# BottomButtonBoard.net
KiCad netlist of a schematic drawn in EAGLE
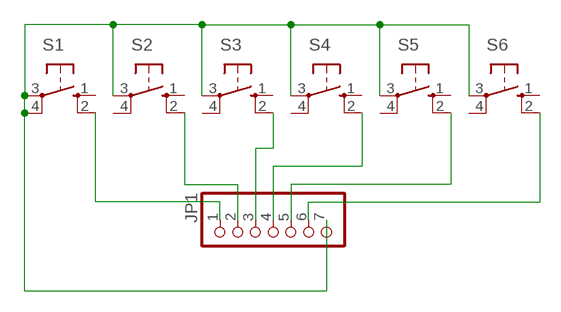
[diagram p0: schematic, sheet 1]

(export (version "E")
  (design (tool "Eeschema 10.0.6"))
  (components
    (comp (ref "JP1")
      (value "PINHD-1X7")
      (footprint "eagle-import:1X07")
      (libsource (lib "eagle-import") (part "PINHD-1X7"))
    )
    (comp (ref "S1")
      (value "10-XX")
      (footprint "eagle-import:B3F-10XX")
      (fields (field (name "MPN") "B3F-1000"))
      (libsource (lib "eagle-import") (part "10-XX"))
    )
    (comp (ref "S2")
      (value "10-XX")
      (footprint "eagle-import:B3F-10XX")
      (fields (field (name "MPN") "B3F-1000"))
      (libsource (lib "eagle-import") (part "10-XX"))
    )
    (comp (ref "S3")
      (value "10-XX")
      (footprint "eagle-import:B3F-10XX")
      (fields (field (name "MPN") "B3F-1000"))
      (libsource (lib "eagle-import") (part "10-XX"))
    )
    (comp (ref "S4")
      (value "10-XX")
      (footprint "eagle-import:B3F-10XX")
      (fields (field (name "MPN") "B3F-1000"))
      (libsource (lib "eagle-import") (part "10-XX"))
    )
    (comp (ref "S5")
      (value "10-XX")
      (footprint "eagle-import:B3F-10XX")
      (fields (field (name "MPN") "B3F-1000"))
      (libsource (lib "eagle-import") (part "10-XX"))
    )
    (comp (ref "S6")
      (value "10-XX")
      (footprint "eagle-import:B3F-10XX")
      (fields (field (name "MPN") "B3F-1000"))
      (libsource (lib "eagle-import") (part "10-XX"))
    )
  )
  (nets
    (net (code "1") (name "Net-(S1-P)") (class "Default")
      (node (ref "JP1") (pin "7") (pinfunction "7_7") (pintype "passive"))
      (node (ref "S1") (pin "3") (pinfunction "P_3") (pintype "passive"))
      (node (ref "S1") (pin "4") (pinfunction "P1_4") (pintype "passive"))
      (node (ref "S2") (pin "3") (pinfunction "P_3") (pintype "passive"))
      (node (ref "S3") (pin "3") (pinfunction "P_3") (pintype "passive"))
      (node (ref "S4") (pin "3") (pinfunction "P_3") (pintype "passive"))
      (node (ref "S5") (pin "3") (pinfunction "P_3") (pintype "passive"))
      (node (ref "S6") (pin "3") (pinfunction "P_3") (pintype "passive"))
    )
    (net (code "2") (name "Net-(S1-S1)") (class "Default")
      (node (ref "JP1") (pin "1") (pinfunction "1_1") (pintype "passive"))
      (node (ref "S1") (pin "2") (pinfunction "S1_2") (pintype "passive"))
    )
    (net (code "3") (name "Net-(S2-S1)") (class "Default")
      (node (ref "JP1") (pin "2") (pinfunction "2_2") (pintype "passive"))
      (node (ref "S2") (pin "2") (pinfunction "S1_2") (pintype "passive"))
    )
    (net (code "4") (name "Net-(S3-S1)") (class "Default")
      (node (ref "JP1") (pin "3") (pinfunction "3_3") (pintype "passive"))
      (node (ref "S3") (pin "2") (pinfunction "S1_2") (pintype "passive"))
    )
    (net (code "5") (name "Net-(S4-S1)") (class "Default")
      (node (ref "JP1") (pin "4") (pinfunction "4_4") (pintype "passive"))
      (node (ref "S4") (pin "2") (pinfunction "S1_2") (pintype "passive"))
    )
    (net (code "6") (name "Net-(S5-S1)") (class "Default")
      (node (ref "JP1") (pin "5") (pinfunction "5_5") (pintype "passive"))
      (node (ref "S5") (pin "2") (pinfunction "S1_2") (pintype "passive"))
    )
    (net (code "7") (name "Net-(S6-S1)") (class "Default")
      (node (ref "JP1") (pin "6") (pinfunction "6_6") (pintype "passive"))
      (node (ref "S6") (pin "2") (pinfunction "S1_2") (pintype "passive"))
    )
    (net (code "8") (name "unconnected-(S1-S-Pad1)") (class "Default")
      (node (ref "S1") (pin "1") (pinfunction "S_1") (pintype "passive"))
    )
    (net (code "9") (name "unconnected-(S2-P1-Pad4)") (class "Default")
      (node (ref "S2") (pin "4") (pinfunction "P1_4") (pintype "passive"))
    )
    (net (code "10") (name "unconnected-(S2-S-Pad1)") (class "Default")
      (node (ref "S2") (pin "1") (pinfunction "S_1") (pintype "passive"))
    )
    (net (code "11") (name "unconnected-(S3-P1-Pad4)") (class "Default")
      (node (ref "S3") (pin "4") (pinfunction "P1_4") (pintype "passive"))
    )
    (net (code "12") (name "unconnected-(S3-S-Pad1)") (class "Default")
      (node (ref "S3") (pin "1") (pinfunction "S_1") (pintype "passive"))
    )
    (net (code "13") (name "unconnected-(S4-P1-Pad4)") (class "Default")
      (node (ref "S4") (pin "4") (pinfunction "P1_4") (pintype "passive"))
    )
    (net (code "14") (name "unconnected-(S4-S-Pad1)") (class "Default")
      (node (ref "S4") (pin "1") (pinfunction "S_1") (pintype "passive"))
    )
    (net (code "15") (name "unconnected-(S5-P1-Pad4)") (class "Default")
      (node (ref "S5") (pin "4") (pinfunction "P1_4") (pintype "passive"))
    )
    (net (code "16") (name "unconnected-(S5-S-Pad1)") (class "Default")
      (node (ref "S5") (pin "1") (pinfunction "S_1") (pintype "passive"))
    )
    (net (code "17") (name "unconnected-(S6-P1-Pad4)") (class "Default")
      (node (ref "S6") (pin "4") (pinfunction "P1_4") (pintype "passive"))
    )
    (net (code "18") (name "unconnected-(S6-S-Pad1)") (class "Default")
      (node (ref "S6") (pin "1") (pinfunction "S_1") (pintype "passive"))
    )
  )
)
